# CPU.net
KiCad netlist of a schematic drawn in Altium Designer
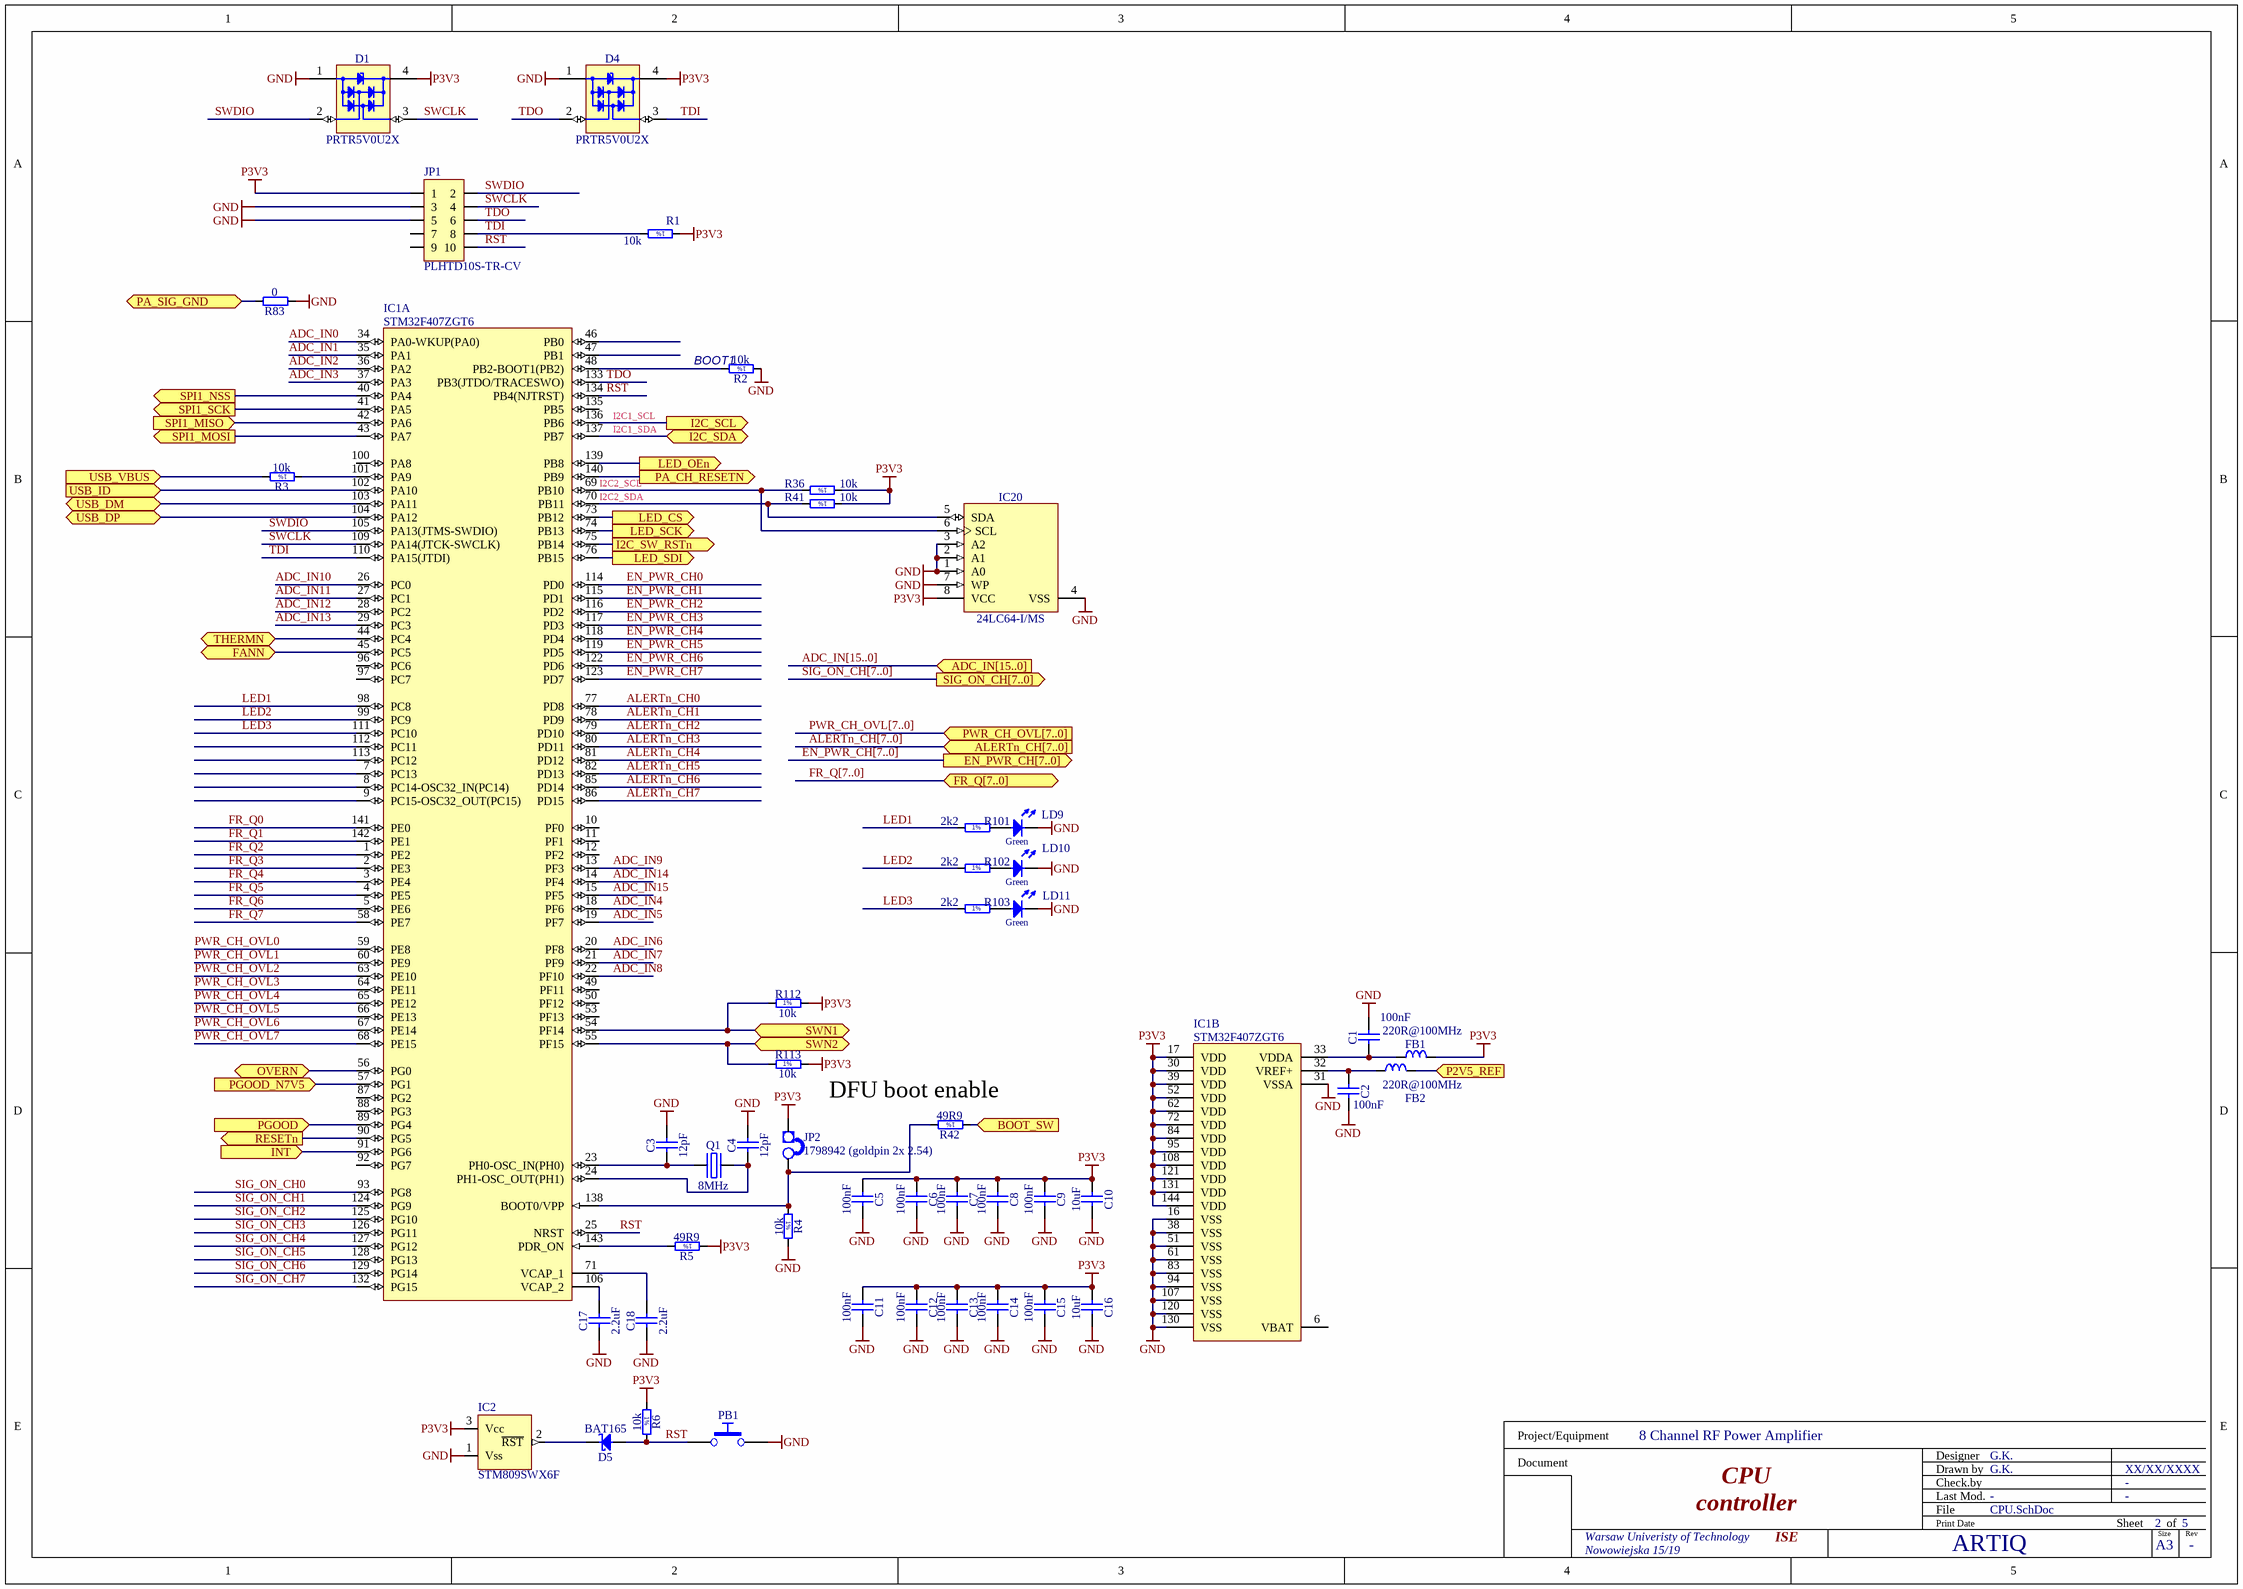
[diagram p0: CPU.SchDoc]

(export (version "E")
  (design (tool "Eeschema 10.0.6"))
  (components
    (comp (ref "C1")
      (value "100nF")
      (footprint "CAPC1005X55N")
      (description "Non-polarised capacitor")
      (fields
        (field (name "PART NUMBER") "CC0402_100NF_16V_10%_X7R")
        (field (name "VOLTAGE") "16V")
        (field (name "AUTHOR") "CERN DEM JLC")
      )
      (libsource (lib "Capacitors") (part "Capacitor - non polarized"))
    )
    (comp (ref "C2")
      (value "100nF")
      (footprint "CAPC1005X55N")
      (description "Non-polarised capacitor")
      (fields
        (field (name "PART NUMBER") "CC0402_100NF_16V_10%_X7R")
        (field (name "VOLTAGE") "16V")
        (field (name "AUTHOR") "CERN DEM JLC")
      )
      (libsource (lib "Capacitors") (part "Capacitor - non polarized"))
    )
    (comp (ref "C3")
      (value "12pF")
      (footprint "CAPC1005X55N")
      (description "Non-polarised capacitor")
      (fields
        (field (name "PART NUMBER") "CC0402_12PF_50V_5%_C0G")
        (field (name "VOLTAGE") "50V")
        (field (name "AUTHOR") "CERN DEM JLC")
      )
      (libsource (lib "Capacitors") (part "Capacitor - non polarized"))
    )
    (comp (ref "C4")
      (value "12pF")
      (footprint "CAPC1005X55N")
      (description "Non-polarised capacitor")
      (fields
        (field (name "PART NUMBER") "CC0402_12PF_50V_5%_C0G")
        (field (name "VOLTAGE") "50V")
        (field (name "AUTHOR") "CERN DEM JLC")
      )
      (libsource (lib "Capacitors") (part "Capacitor - non polarized"))
    )
    (comp (ref "C5")
      (value "100nF")
      (footprint "CAPC1005X55N")
      (description "Non-polarised capacitor")
      (fields
        (field (name "PART NUMBER") "CC0402_100NF_16V_10%_X7R")
        (field (name "VOLTAGE") "16V")
        (field (name "AUTHOR") "CERN DEM JLC")
      )
      (libsource (lib "Capacitors") (part "Capacitor - non polarized"))
    )
    (comp (ref "C6")
      (value "100nF")
      (footprint "CAPC1005X55N")
      (description "Non-polarised capacitor")
      (fields
        (field (name "PART NUMBER") "CC0402_100NF_16V_10%_X7R")
        (field (name "VOLTAGE") "16V")
        (field (name "AUTHOR") "CERN DEM JLC")
      )
      (libsource (lib "Capacitors") (part "Capacitor - non polarized"))
    )
    (comp (ref "C7")
      (value "100nF")
      (footprint "CAPC1005X55N")
      (description "Non-polarised capacitor")
      (fields
        (field (name "PART NUMBER") "CC0402_100NF_16V_10%_X7R")
        (field (name "VOLTAGE") "16V")
        (field (name "AUTHOR") "CERN DEM JLC")
      )
      (libsource (lib "Capacitors") (part "Capacitor - non polarized"))
    )
    (comp (ref "C8")
      (value "100nF")
      (footprint "CAPC1005X55N")
      (description "Non-polarised capacitor")
      (fields
        (field (name "PART NUMBER") "CC0402_100NF_16V_10%_X7R")
        (field (name "VOLTAGE") "16V")
        (field (name "AUTHOR") "CERN DEM JLC")
      )
      (libsource (lib "Capacitors") (part "Capacitor - non polarized"))
    )
    (comp (ref "C9")
      (value "100nF")
      (footprint "CAPC1005X55N")
      (description "Non-polarised capacitor")
      (fields
        (field (name "PART NUMBER") "CC0402_100NF_16V_10%_X7R")
        (field (name "VOLTAGE") "16V")
        (field (name "AUTHOR") "CERN DEM JLC")
      )
      (libsource (lib "Capacitors") (part "Capacitor - non polarized"))
    )
    (comp (ref "C10")
      (value "10uF")
      (footprint "CAPC2012X135N")
      (description "Non-polarised capacitor")
      (fields
        (field (name "PART NUMBER") "CC0805_10UF_16V_10%_X5R")
        (field (name "VOLTAGE") "16V")
        (field (name "AUTHOR") "CERN DEM JLC")
      )
      (libsource (lib "Capacitors") (part "Capacitor - non polarized"))
    )
    (comp (ref "C11")
      (value "100nF")
      (footprint "CAPC1005X55N")
      (description "Non-polarised capacitor")
      (fields
        (field (name "PART NUMBER") "CC0402_100NF_16V_10%_X7R")
        (field (name "VOLTAGE") "16V")
        (field (name "AUTHOR") "CERN DEM JLC")
      )
      (libsource (lib "Capacitors") (part "Capacitor - non polarized"))
    )
    (comp (ref "C12")
      (value "100nF")
      (footprint "CAPC1005X55N")
      (description "Non-polarised capacitor")
      (fields
        (field (name "PART NUMBER") "CC0402_100NF_16V_10%_X7R")
        (field (name "VOLTAGE") "16V")
        (field (name "AUTHOR") "CERN DEM JLC")
      )
      (libsource (lib "Capacitors") (part "Capacitor - non polarized"))
    )
    (comp (ref "C13")
      (value "100nF")
      (footprint "CAPC1005X55N")
      (description "Non-polarised capacitor")
      (fields
        (field (name "PART NUMBER") "CC0402_100NF_16V_10%_X7R")
        (field (name "VOLTAGE") "16V")
        (field (name "AUTHOR") "CERN DEM JLC")
      )
      (libsource (lib "Capacitors") (part "Capacitor - non polarized"))
    )
    (comp (ref "C14")
      (value "100nF")
      (footprint "CAPC1005X55N")
      (description "Non-polarised capacitor")
      (fields
        (field (name "PART NUMBER") "CC0402_100NF_16V_10%_X7R")
        (field (name "VOLTAGE") "16V")
        (field (name "AUTHOR") "CERN DEM JLC")
      )
      (libsource (lib "Capacitors") (part "Capacitor - non polarized"))
    )
    (comp (ref "C15")
      (value "100nF")
      (footprint "CAPC1005X55N")
      (description "Non-polarised capacitor")
      (fields
        (field (name "PART NUMBER") "CC0402_100NF_16V_10%_X7R")
        (field (name "VOLTAGE") "16V")
        (field (name "AUTHOR") "CERN DEM JLC")
      )
      (libsource (lib "Capacitors") (part "Capacitor - non polarized"))
    )
    (comp (ref "C16")
      (value "10uF")
      (footprint "CAPC2012X135N")
      (description "Non-polarised capacitor")
      (fields
        (field (name "PART NUMBER") "CC0805_10UF_16V_10%_X5R")
        (field (name "VOLTAGE") "16V")
        (field (name "AUTHOR") "CERN DEM JLC")
      )
      (libsource (lib "Capacitors") (part "Capacitor - non polarized"))
    )
    (comp (ref "C17")
      (value "2.2uF")
      (footprint "CAPC1608X90N")
      (description "Non-polarised capacitor")
      (fields
        (field (name "PART NUMBER") "CC0603_2.2UF_10V_20%_X7R")
        (field (name "VOLTAGE") "10V")
        (field (name "AUTHOR") "CERN DEM JLC")
      )
      (libsource (lib "Capacitors") (part "Capacitor - non polarized"))
    )
    (comp (ref "C18")
      (value "2.2uF")
      (footprint "CAPC1608X90N")
      (description "Non-polarised capacitor")
      (fields
        (field (name "PART NUMBER") "CC0603_2.2UF_10V_20%_X7R")
        (field (name "VOLTAGE") "10V")
        (field (name "AUTHOR") "CERN DEM JLC")
      )
      (libsource (lib "Capacitors") (part "Capacitor - non polarized"))
    )
    (comp (ref "D1")
      (value "PRTR5V0U2X")
      (footprint "SOT190P230X110-4N")
      (description "Ultra Low Capacitance Double Rail-to-Rail ESD Protection Diode")
      (fields
        (field (name "VOLTAGE") "5.5V")
        (field (name "MANUFACTURER") "NXP SEMICONDUCTORS")
        (field (name "AUTHOR") "CERN DEM JLC")
      )
      (libsource (lib "ICs And Semiconductors") (part "PRTR5V0U2X"))
    )
    (comp (ref "D4")
      (value "PRTR5V0U2X")
      (footprint "SOT190P230X110-4N")
      (description "Ultra Low Capacitance Double Rail-to-Rail ESD Protection Diode")
      (fields
        (field (name "VOLTAGE") "5.5V")
        (field (name "MANUFACTURER") "NXP SEMICONDUCTORS")
        (field (name "AUTHOR") "CERN DEM JLC")
      )
      (libsource (lib "ICs And Semiconductors") (part "PRTR5V0U2X"))
    )
    (comp (ref "D5")
      (value "BAT165")
      (footprint "SOD2512X110N")
      (description "Schottky Diode")
      (fields
        (field (name "VOLTAGE") "40V")
        (field (name "POWER") "750mA")
        (field (name "AUTHOR") "CERN DEM JLC")
      )
      (libsource (lib "ICs And Semiconductors") (part "Diode Schottky"))
    )
    (comp (ref "FB1")
      (value "220R@100MHz")
      (footprint "INDC2012X105N")
      (description "Inductor")
      (fields
        (field (name "PART NUMBER") "IND0805_MURATA_BLM21PG221SN1D")
        (field (name "POWER") "2A")
        (field (name "AUTHOR") "CERN DEM JLC")
      )
      (libsource (lib "Inductors & Transformers") (part "Inductor"))
    )
    (comp (ref "FB2")
      (value "220R@100MHz")
      (footprint "INDC2012X105N")
      (description "Inductor")
      (fields
        (field (name "PART NUMBER") "IND0805_MURATA_BLM21PG221SN1D")
        (field (name "POWER") "2A")
        (field (name "AUTHOR") "CERN DEM JLC")
      )
      (libsource (lib "Inductors & Transformers") (part "Inductor"))
    )
    (comp (ref "IC1")
      (value "STM32F407ZGT6")
      (footprint "QFP50P2200X2200X160-144N")
      (fields (field (name "MANUFACTURER") "ST MICROELECTRONICS") (field (name "AUTHOR") "CERN DEM MR"))
      (libsource (lib "ICs And Semiconductors") (part "STM32F407ZGT6"))
    )
    (comp (ref "IC2")
      (value "STM809SWX6F")
      (footprint "SOT-23")
      (description "2.93V  Reset circuit")
      (libsource (lib "LIBRARY_SCH") (part "VMON_STM809"))
    )
    (comp (ref "IC20")
      (value "24LC64-I/MS")
      (footprint "SOP65P490X110-8N")
      (description "64K I2C Serial EEPROM")
      (fields (field (name "MANUFACTURER") "MICROCHIP TECHNOLOGY") (field (name "AUTHOR") "CERN DEM JLC"))
      (libsource (lib "ICs And Semiconductors") (part "24LC64-I/MS"))
    )
    (comp (ref "JP1")
      (value "PLHTD10S-TR-CV")
      (footprint "PLHTD10S-TR-CV")
      (description "1.27 mm dual row goldpin (Maritex)")
      (libsource (lib "LIBRARY_SCH") (part "CON_2x5 1.27 SMT Male"))
    )
    (comp (ref "JP2")
      (value "1798942 (goldpin 2x 2.54)")
      (footprint "jump")
      (description "Jumper")
      (libsource (lib "LIBRARY_SCH") (part "JUMPER"))
    )
    (comp (ref "LD9")
      (value "Green")
      (footprint "LED_OSRAM_LGL29K")
      (description "LED Green 1C 2A")
      (fields
        (field (name "PART NUMBER") "LED_OSRAM_LG L29K-G2J1-24-Z")
        (field (name "MANUFACTURER") "OSRAM")
        (field (name "AUTHOR") "CERN DEM JLC")
      )
      (libsource (lib "ICs And Semiconductors") (part "LED Green 1C 2A"))
    )
    (comp (ref "LD10")
      (value "Green")
      (footprint "LED_OSRAM_LGL29K")
      (description "LED Green 1C 2A")
      (fields
        (field (name "PART NUMBER") "LED_OSRAM_LG L29K-G2J1-24-Z")
        (field (name "MANUFACTURER") "OSRAM")
        (field (name "AUTHOR") "CERN DEM JLC")
      )
      (libsource (lib "ICs And Semiconductors") (part "LED Green 1C 2A"))
    )
    (comp (ref "LD11")
      (value "Green")
      (footprint "LED_OSRAM_LGL29K")
      (description "LED Green 1C 2A")
      (fields
        (field (name "PART NUMBER") "LED_OSRAM_LG L29K-G2J1-24-Z")
        (field (name "MANUFACTURER") "OSRAM")
        (field (name "AUTHOR") "CERN DEM JLC")
      )
      (libsource (lib "ICs And Semiconductors") (part "LED Green 1C 2A"))
    )
    (comp (ref "PB1")
      (value "Push Button")
      (footprint "PB_TYCO_FSMSM")
      (description "Push-Button Switch SPDT")
      (fields
        (field (name "PART NUMBER") "PB_TYCO_FSMSM")
        (field (name "MANUFACTURER") "TYCO ELECTRONICS")
        (field (name "AUTHOR") "CERN DEM JLC")
      )
      (libsource (lib "Eletro-mechanical") (part "PB SPST 1NO-2NO"))
    )
    (comp (ref "Q1")
      (value "8MHz")
      (footprint "XTAL_TXC_7A")
      (description "Quartz Crystal")
      (fields
        (field (name "PART NUMBER") "XTAL_8MHZ_TXC_7A-8.000MAAE-T")
        (field (name "MANUFACTURER") "TXC CORPORATION")
        (field (name "AUTHOR") "CERN DEM JLC")
      )
      (libsource (lib "ICs And Semiconductors") (part "Quartz Crystal"))
    )
    (comp (ref "R1")
      (value "10k")
      (footprint "RESC1005X40N")
      (description "Resistor - 1%")
      (fields
        (field (name "PART NUMBER") "R0402_10K_1%_0.0625W_100PPM")
        (field (name "POWER") "0.0625W")
        (field (name "AUTHOR") "CERN DEM JLC")
      )
      (libsource (lib "Resistors") (part "Resistor - 1%"))
    )
    (comp (ref "R2")
      (value "10k")
      (footprint "RESC1005X40N")
      (description "Resistor - 1%")
      (fields
        (field (name "PART NUMBER") "R0402_10K_1%_0.0625W_100PPM")
        (field (name "POWER") "0.0625W")
        (field (name "AUTHOR") "CERN DEM JLC")
      )
      (libsource (lib "Resistors") (part "Resistor - 1%"))
    )
    (comp (ref "R3")
      (value "10k")
      (footprint "RESC1005X40N")
      (description "Resistor - 1%")
      (fields
        (field (name "PART NUMBER") "R0402_10K_1%_0.0625W_100PPM")
        (field (name "POWER") "0.0625W")
        (field (name "AUTHOR") "CERN DEM JLC")
      )
      (libsource (lib "Resistors") (part "Resistor - 1%"))
    )
    (comp (ref "R4")
      (value "10k")
      (footprint "RESC1005X40N")
      (description "Resistor - 1%")
      (fields
        (field (name "PART NUMBER") "R0402_10K_1%_0.0625W_100PPM")
        (field (name "POWER") "0.0625W")
        (field (name "AUTHOR") "CERN DEM JLC")
      )
      (libsource (lib "Resistors") (part "Resistor - 1%"))
    )
    (comp (ref "R5")
      (value "49R9")
      (footprint "RESC1005X40N")
      (description "Resistor - 1%")
      (fields
        (field (name "PART NUMBER") "R0402_49R9_1%_0.0625W_100PPM")
        (field (name "POWER") "0.0625W")
        (field (name "AUTHOR") "CERN DEM JLC")
      )
      (libsource (lib "Resistors") (part "Resistor - 1%"))
    )
    (comp (ref "R6")
      (value "10k")
      (footprint "RESC1005X40N")
      (description "Resistor - 1%")
      (fields
        (field (name "PART NUMBER") "R0402_10K_1%_0.0625W_100PPM")
        (field (name "POWER") "0.0625W")
        (field (name "AUTHOR") "CERN DEM JLC")
      )
      (libsource (lib "Resistors") (part "Resistor - 1%"))
    )
    (comp (ref "R36")
      (value "10k")
      (footprint "RESC1005X40N")
      (description "Resistor - 1%")
      (fields
        (field (name "PART NUMBER") "R0402_10K_1%_0.0625W_100PPM")
        (field (name "POWER") "0.0625W")
        (field (name "AUTHOR") "CERN DEM JLC")
      )
      (libsource (lib "Resistors") (part "Resistor - 1%"))
    )
    (comp (ref "R41")
      (value "10k")
      (footprint "RESC1005X40N")
      (description "Resistor - 1%")
      (fields
        (field (name "PART NUMBER") "R0402_10K_1%_0.0625W_100PPM")
        (field (name "POWER") "0.0625W")
        (field (name "AUTHOR") "CERN DEM JLC")
      )
      (libsource (lib "Resistors") (part "Resistor - 1%"))
    )
    (comp (ref "R42")
      (value "49R9")
      (footprint "RESC1005X40N")
      (description "Resistor - 1%")
      (fields
        (field (name "PART NUMBER") "R0402_49R9_1%_0.0625W_100PPM")
        (field (name "POWER") "0.0625W")
        (field (name "AUTHOR") "CERN DEM JLC")
      )
      (libsource (lib "Resistors") (part "Resistor - 1%"))
    )
    (comp (ref "R83")
      (value "0")
      (footprint "RESC1005X40N")
      (description "Resistor")
      (fields
        (field (name "PART NUMBER") "R0402_0R_JUMPER")
        (field (name "MANUFACTURER") "GENERIC")
        (field (name "AUTHOR") "CERN DEM JLC")
      )
      (libsource (lib "Resistors") (part "Resistor"))
    )
    (comp (ref "R101")
      (value "2k2")
      (footprint "RESC1005X40N")
      (description "Resistor - 1%")
      (fields
        (field (name "PART NUMBER") "R0402_2K2_1%_0.0625W_100PPM")
        (field (name "POWER") "0.0625W")
        (field (name "AUTHOR") "CERN DEM JLC")
      )
      (libsource (lib "Resistors") (part "Resistor - 1%"))
    )
    (comp (ref "R102")
      (value "2k2")
      (footprint "RESC1005X40N")
      (description "Resistor - 1%")
      (fields
        (field (name "PART NUMBER") "R0402_2K2_1%_0.0625W_100PPM")
        (field (name "POWER") "0.0625W")
        (field (name "AUTHOR") "CERN DEM JLC")
      )
      (libsource (lib "Resistors") (part "Resistor - 1%"))
    )
    (comp (ref "R103")
      (value "2k2")
      (footprint "RESC1005X40N")
      (description "Resistor - 1%")
      (fields
        (field (name "PART NUMBER") "R0402_2K2_1%_0.0625W_100PPM")
        (field (name "POWER") "0.0625W")
        (field (name "AUTHOR") "CERN DEM JLC")
      )
      (libsource (lib "Resistors") (part "Resistor - 1%"))
    )
    (comp (ref "R112")
      (value "10k")
      (footprint "RESC1005X40N")
      (description "Resistor - 1%")
      (fields
        (field (name "PART NUMBER") "R0402_10K_1%_0.0625W_100PPM")
        (field (name "POWER") "0.0625W")
        (field (name "AUTHOR") "CERN DEM JLC")
      )
      (libsource (lib "Resistors") (part "Resistor - 1%"))
    )
    (comp (ref "R113")
      (value "10k")
      (footprint "RESC1005X40N")
      (description "Resistor - 1%")
      (fields
        (field (name "PART NUMBER") "R0402_10K_1%_0.0625W_100PPM")
        (field (name "POWER") "0.0625W")
        (field (name "AUTHOR") "CERN DEM JLC")
      )
      (libsource (lib "Resistors") (part "Resistor - 1%"))
    )
  )
  (nets
    (net (code "1") (name "/ADC_IN0") (class "Default")
      (node (ref "IC1") (pin "34") (pinfunction "PA0-WKUP(PA0)_34") (pintype "bidirectional"))
    )
    (net (code "2") (name "/ADC_IN1") (class "Default")
      (node (ref "IC1") (pin "35") (pinfunction "PA1_35") (pintype "bidirectional"))
    )
    (net (code "3") (name "/ADC_IN2") (class "Default")
      (node (ref "IC1") (pin "36") (pinfunction "PA2_36") (pintype "bidirectional"))
    )
    (net (code "4") (name "/ADC_IN3") (class "Default")
      (node (ref "IC1") (pin "37") (pinfunction "PA3_37") (pintype "bidirectional"))
    )
    (net (code "5") (name "/ADC_IN4") (class "Default")
      (node (ref "IC1") (pin "18") (pinfunction "PF6_18") (pintype "bidirectional"))
    )
    (net (code "6") (name "/ADC_IN5") (class "Default")
      (node (ref "IC1") (pin "19") (pinfunction "PF7_19") (pintype "bidirectional"))
    )
    (net (code "7") (name "/ADC_IN6") (class "Default")
      (node (ref "IC1") (pin "20") (pinfunction "PF8_20") (pintype "bidirectional"))
    )
    (net (code "8") (name "/ADC_IN7") (class "Default")
      (node (ref "IC1") (pin "21") (pinfunction "PF9_21") (pintype "bidirectional"))
    )
    (net (code "9") (name "/ADC_IN8") (class "Default")
      (node (ref "IC1") (pin "22") (pinfunction "PF10_22") (pintype "bidirectional"))
    )
    (net (code "10") (name "/ADC_IN9") (class "Default")
      (node (ref "IC1") (pin "13") (pinfunction "PF3_13") (pintype "bidirectional"))
    )
    (net (code "11") (name "/ADC_IN10") (class "Default")
      (node (ref "IC1") (pin "26") (pinfunction "PC0_26") (pintype "bidirectional"))
    )
    (net (code "12") (name "/ADC_IN11") (class "Default")
      (node (ref "IC1") (pin "27") (pinfunction "PC1_27") (pintype "bidirectional"))
    )
    (net (code "13") (name "/ADC_IN12") (class "Default")
      (node (ref "IC1") (pin "28") (pinfunction "PC2_28") (pintype "bidirectional"))
    )
    (net (code "14") (name "/ADC_IN13") (class "Default")
      (node (ref "IC1") (pin "29") (pinfunction "PC3_29") (pintype "bidirectional"))
    )
    (net (code "15") (name "/ADC_IN14") (class "Default")
      (node (ref "IC1") (pin "14") (pinfunction "PF4_14") (pintype "bidirectional"))
    )
    (net (code "16") (name "/ADC_IN15") (class "Default")
      (node (ref "IC1") (pin "15") (pinfunction "PF5_15") (pintype "bidirectional"))
    )
    (net (code "18") (name "/ALERTn_CH0") (class "Default")
      (node (ref "IC1") (pin "77") (pinfunction "PD8_77") (pintype "bidirectional"))
    )
    (net (code "19") (name "/ALERTn_CH1") (class "Default")
      (node (ref "IC1") (pin "78") (pinfunction "PD9_78") (pintype "bidirectional"))
    )
    (net (code "20") (name "/ALERTn_CH2") (class "Default")
      (node (ref "IC1") (pin "79") (pinfunction "PD10_79") (pintype "bidirectional"))
    )
    (net (code "21") (name "/ALERTn_CH3") (class "Default")
      (node (ref "IC1") (pin "80") (pinfunction "PD11_80") (pintype "bidirectional"))
    )
    (net (code "22") (name "/ALERTn_CH4") (class "Default")
      (node (ref "IC1") (pin "81") (pinfunction "PD12_81") (pintype "bidirectional"))
    )
    (net (code "23") (name "/ALERTn_CH5") (class "Default")
      (node (ref "IC1") (pin "82") (pinfunction "PD13_82") (pintype "bidirectional"))
    )
    (net (code "24") (name "/ALERTn_CH6") (class "Default")
      (node (ref "IC1") (pin "85") (pinfunction "PD14_85") (pintype "bidirectional"))
    )
    (net (code "25") (name "/ALERTn_CH7") (class "Default")
      (node (ref "IC1") (pin "86") (pinfunction "PD15_86") (pintype "bidirectional"))
    )
    (net (code "27") (name "/BOOT_SW") (class "Default")
      (node (ref "R42") (pin "1") (pinfunction "1_1") (pintype "passive"))
    )
    (net (code "28") (name "/EN_PWR_CH0") (class "Default")
      (node (ref "IC1") (pin "114") (pinfunction "PD0_114") (pintype "bidirectional"))
    )
    (net (code "29") (name "/EN_PWR_CH1") (class "Default")
      (node (ref "IC1") (pin "115") (pinfunction "PD1_115") (pintype "bidirectional"))
    )
    (net (code "30") (name "/EN_PWR_CH2") (class "Default")
      (node (ref "IC1") (pin "116") (pinfunction "PD2_116") (pintype "bidirectional"))
    )
    (net (code "31") (name "/EN_PWR_CH3") (class "Default")
      (node (ref "IC1") (pin "117") (pinfunction "PD3_117") (pintype "bidirectional"))
    )
    (net (code "32") (name "/EN_PWR_CH4") (class "Default")
      (node (ref "IC1") (pin "118") (pinfunction "PD4_118") (pintype "bidirectional"))
    )
    (net (code "33") (name "/EN_PWR_CH5") (class "Default")
      (node (ref "IC1") (pin "119") (pinfunction "PD5_119") (pintype "bidirectional"))
    )
    (net (code "34") (name "/EN_PWR_CH6") (class "Default")
      (node (ref "IC1") (pin "122") (pinfunction "PD6_122") (pintype "bidirectional"))
    )
    (net (code "35") (name "/EN_PWR_CH7") (class "Default")
      (node (ref "IC1") (pin "123") (pinfunction "PD7_123") (pintype "bidirectional"))
    )
    (net (code "37") (name "/FANN") (class "Default")
      (node (ref "IC1") (pin "45") (pinfunction "PC5_45") (pintype "bidirectional"))
    )
    (net (code "38") (name "/FR_Q0") (class "Default")
      (node (ref "IC1") (pin "141") (pinfunction "PE0_141") (pintype "bidirectional"))
    )
    (net (code "39") (name "/FR_Q1") (class "Default")
      (node (ref "IC1") (pin "142") (pinfunction "PE1_142") (pintype "bidirectional"))
    )
    (net (code "40") (name "/FR_Q2") (class "Default")
      (node (ref "IC1") (pin "1") (pinfunction "PE2_1") (pintype "bidirectional"))
    )
    (net (code "41") (name "/FR_Q3") (class "Default")
      (node (ref "IC1") (pin "2") (pinfunction "PE3_2") (pintype "bidirectional"))
    )
    (net (code "42") (name "/FR_Q4") (class "Default")
      (node (ref "IC1") (pin "3") (pinfunction "PE4_3") (pintype "bidirectional"))
    )
    (net (code "43") (name "/FR_Q5") (class "Default")
      (node (ref "IC1") (pin "4") (pinfunction "PE5_4") (pintype "bidirectional"))
    )
    (net (code "44") (name "/FR_Q6") (class "Default")
      (node (ref "IC1") (pin "5") (pinfunction "PE6_5") (pintype "bidirectional"))
    )
    (net (code "45") (name "/FR_Q7") (class "Default")
      (node (ref "IC1") (pin "58") (pinfunction "PE7_58") (pintype "bidirectional"))
    )
    (net (code "47") (name "/I2C_SCL") (class "Default")
      (node (ref "IC1") (pin "136") (pinfunction "PB6_136") (pintype "bidirectional"))
    )
    (net (code "48") (name "/I2C_SDA") (class "Default")
      (node (ref "IC1") (pin "137") (pinfunction "PB7_137") (pintype "bidirectional"))
    )
    (net (code "49") (name "/I2C_SW_RSTn") (class "Default")
      (node (ref "IC1") (pin "75") (pinfunction "PB14_75") (pintype "bidirectional"))
    )
    (net (code "50") (name "/INT") (class "Default")
      (node (ref "IC1") (pin "91") (pinfunction "PG6_91") (pintype "bidirectional"))
    )
    (net (code "51") (name "/LED1") (class "Default")
      (node (ref "IC1") (pin "98") (pinfunction "PC8_98") (pintype "bidirectional"))
      (node (ref "R101") (pin "1") (pinfunction "1_1") (pintype "passive"))
    )
    (net (code "52") (name "/LED2") (class "Default")
      (node (ref "IC1") (pin "99") (pinfunction "PC9_99") (pintype "bidirectional"))
      (node (ref "R102") (pin "1") (pinfunction "1_1") (pintype "passive"))
    )
    (net (code "53") (name "/LED3") (class "Default")
      (node (ref "IC1") (pin "111") (pinfunction "PC10_111") (pintype "bidirectional"))
      (node (ref "R103") (pin "1") (pinfunction "1_1") (pintype "passive"))
    )
    (net (code "54") (name "/LED_CS") (class "Default")
      (node (ref "IC1") (pin "73") (pinfunction "PB12_73") (pintype "bidirectional"))
    )
    (net (code "55") (name "/LED_OEn") (class "Default")
      (node (ref "IC1") (pin "139") (pinfunction "PB8_139") (pintype "bidirectional"))
    )
    (net (code "56") (name "/LED_SCK") (class "Default")
      (node (ref "IC1") (pin "74") (pinfunction "PB13_74") (pintype "bidirectional"))
    )
    (net (code "57") (name "/LED_SDI") (class "Default")
      (node (ref "IC1") (pin "76") (pinfunction "PB15_76") (pintype "bidirectional"))
    )
    (net (code "58") (name "/OVERN") (class "Default")
      (node (ref "IC1") (pin "56") (pinfunction "PG0_56") (pintype "bidirectional"))
    )
    (net (code "59") (name "/P2V5_REF") (class "Default")
      (node (ref "FB2") (pin "2") (pinfunction "2_2") (pintype "passive"))
    )
    (net (code "60") (name "/PA_CH_RESETN") (class "Default")
      (node (ref "IC1") (pin "140") (pinfunction "PB9_140") (pintype "bidirectional"))
    )
    (net (code "61") (name "/PA_SIG_GND") (class "Default")
      (node (ref "R83") (pin "2") (pinfunction "2_2") (pintype "passive"))
    )
    (net (code "62") (name "/PGOOD") (class "Default")
      (node (ref "IC1") (pin "89") (pinfunction "PG4_89") (pintype "bidirectional"))
    )
    (net (code "63") (name "/PGOOD_N7V5") (class "Default")
      (node (ref "IC1") (pin "57") (pinfunction "PG1_57") (pintype "bidirectional"))
    )
    (net (code "64") (name "/PWR_CH_OVL0") (class "Default")
      (node (ref "IC1") (pin "59") (pinfunction "PE8_59") (pintype "bidirectional"))
    )
    (net (code "65") (name "/PWR_CH_OVL1") (class "Default")
      (node (ref "IC1") (pin "60") (pinfunction "PE9_60") (pintype "bidirectional"))
    )
    (net (code "66") (name "/PWR_CH_OVL2") (class "Default")
      (node (ref "IC1") (pin "63") (pinfunction "PE10_63") (pintype "bidirectional"))
    )
    (net (code "67") (name "/PWR_CH_OVL3") (class "Default")
      (node (ref "IC1") (pin "64") (pinfunction "PE11_64") (pintype "bidirectional"))
    )
    (net (code "68") (name "/PWR_CH_OVL4") (class "Default")
      (node (ref "IC1") (pin "65") (pinfunction "PE12_65") (pintype "bidirectional"))
    )
    (net (code "69") (name "/PWR_CH_OVL5") (class "Default")
      (node (ref "IC1") (pin "66") (pinfunction "PE13_66") (pintype "bidirectional"))
    )
    (net (code "70") (name "/PWR_CH_OVL6") (class "Default")
      (node (ref "IC1") (pin "67") (pinfunction "PE14_67") (pintype "bidirectional"))
    )
    (net (code "71") (name "/PWR_CH_OVL7") (class "Default")
      (node (ref "IC1") (pin "68") (pinfunction "PE15_68") (pintype "bidirectional"))
    )
    (net (code "73") (name "/RESETn") (class "Default")
      (node (ref "IC1") (pin "90") (pinfunction "PG5_90") (pintype "bidirectional"))
    )
    (net (code "74") (name "/RST") (class "Default")
      (node (ref "D5") (pin "2") (pinfunction "A_2") (pintype "passive"))
      (node (ref "IC1") (pin "134") (pinfunction "PB4(NJTRST)_134") (pintype "bidirectional"))
      (node (ref "IC1") (pin "25") (pinfunction "NRST_25") (pintype "bidirectional"))
      (node (ref "JP1") (pin "10") (pinfunction "10_10") (pintype "passive"))
      (node (ref "PB1") (pin "1") (pinfunction "1_1") (pintype "passive"))
      (node (ref "R6") (pin "2") (pinfunction "2_2") (pintype "passive"))
    )
    (net (code "75") (name "/SIG_ON_CH0") (class "Default")
      (node (ref "IC1") (pin "93") (pinfunction "PG8_93") (pintype "bidirectional"))
    )
    (net (code "76") (name "/SIG_ON_CH1") (class "Default")
      (node (ref "IC1") (pin "124") (pinfunction "PG9_124") (pintype "bidirectional"))
    )
    (net (code "77") (name "/SIG_ON_CH2") (class "Default")
      (node (ref "IC1") (pin "125") (pinfunction "PG10_125") (pintype "bidirectional"))
    )
    (net (code "78") (name "/SIG_ON_CH3") (class "Default")
      (node (ref "IC1") (pin "126") (pinfunction "PG11_126") (pintype "bidirectional"))
    )
    (net (code "79") (name "/SIG_ON_CH4") (class "Default")
      (node (ref "IC1") (pin "127") (pinfunction "PG12_127") (pintype "bidirectional"))
    )
    (net (code "80") (name "/SIG_ON_CH5") (class "Default")
      (node (ref "IC1") (pin "128") (pinfunction "PG13_128") (pintype "bidirectional"))
    )
    (net (code "81") (name "/SIG_ON_CH6") (class "Default")
      (node (ref "IC1") (pin "129") (pinfunction "PG14_129") (pintype "bidirectional"))
    )
    (net (code "82") (name "/SIG_ON_CH7") (class "Default")
      (node (ref "IC1") (pin "132") (pinfunction "PG15_132") (pintype "bidirectional"))
    )
    (net (code "84") (name "/SPI1_MISO") (class "Default")
      (node (ref "IC1") (pin "42") (pinfunction "PA6_42") (pintype "bidirectional"))
    )
    (net (code "85") (name "/SPI1_MOSI") (class "Default")
      (node (ref "IC1") (pin "43") (pinfunction "PA7_43") (pintype "bidirectional"))
    )
    (net (code "86") (name "/SPI1_NSS") (class "Default")
      (node (ref "IC1") (pin "40") (pinfunction "PA4_40") (pintype "bidirectional"))
    )
    (net (code "87") (name "/SPI1_SCK") (class "Default")
      (node (ref "IC1") (pin "41") (pinfunction "PA5_41") (pintype "bidirectional"))
    )
    (net (code "88") (name "/SWCLK") (class "Default")
      (node (ref "D1") (pin "3") (pinfunction "I/O2_3") (pintype "bidirectional"))
      (node (ref "IC1") (pin "109") (pinfunction "PA14(JTCK-SWCLK)_109") (pintype "bidirectional"))
      (node (ref "JP1") (pin "4") (pinfunction "4_4") (pintype "passive"))
    )
    (net (code "89") (name "/SWDIO") (class "Default")
      (node (ref "D1") (pin "2") (pinfunction "I/O1_2") (pintype "bidirectional"))
      (node (ref "IC1") (pin "105") (pinfunction "PA13(JTMS-SWDIO)_105") (pintype "bidirectional"))
      (node (ref "JP1") (pin "2") (pinfunction "2_2") (pintype "passive"))
    )
    (net (code "90") (name "/SWN1") (class "Default")
      (node (ref "IC1") (pin "54") (pinfunction "PF14_54") (pintype "bidirectional"))
      (node (ref "R112") (pin "1") (pinfunction "1_1") (pintype "passive"))
    )
    (net (code "91") (name "/SWN2") (class "Default")
      (node (ref "IC1") (pin "55") (pinfunction "PF15_55") (pintype "bidirectional"))
      (node (ref "R113") (pin "1") (pinfunction "1_1") (pintype "passive"))
    )
    (net (code "92") (name "/TDI") (class "Default")
      (node (ref "D4") (pin "3") (pinfunction "I/O2_3") (pintype "bidirectional"))
      (node (ref "IC1") (pin "110") (pinfunction "PA15(JTDI)_110") (pintype "bidirectional"))
      (node (ref "JP1") (pin "8") (pinfunction "8_8") (pintype "passive"))
      (node (ref "R1") (pin "2") (pinfunction "2_2") (pintype "passive"))
    )
    (net (code "93") (name "/TDO") (class "Default")
      (node (ref "D4") (pin "2") (pinfunction "I/O1_2") (pintype "bidirectional"))
      (node (ref "IC1") (pin "133") (pinfunction "PB3(JTDO/TRACESWO)_133") (pintype "bidirectional"))
      (node (ref "JP1") (pin "6") (pinfunction "6_6") (pintype "passive"))
    )
    (net (code "94") (name "/THERMN") (class "Default")
      (node (ref "IC1") (pin "44") (pinfunction "PC4_44") (pintype "bidirectional"))
    )
    (net (code "95") (name "/USB_DM") (class "Default")
      (node (ref "IC1") (pin "103") (pinfunction "PA11_103") (pintype "bidirectional"))
    )
    (net (code "96") (name "/USB_DP") (class "Default")
      (node (ref "IC1") (pin "104") (pinfunction "PA12_104") (pintype "bidirectional"))
    )
    (net (code "97") (name "/USB_ID") (class "Default")
      (node (ref "IC1") (pin "102") (pinfunction "PA10_102") (pintype "bidirectional"))
    )
    (net (code "98") (name "/USB_VBUS") (class "Default")
      (node (ref "R3") (pin "2") (pinfunction "2_2") (pintype "passive"))
    )
    (net (code "99") (name "GND") (class "Default")
      (node (ref "C1") (pin "2") (pinfunction "2_2") (pintype "passive"))
      (node (ref "C10") (pin "2") (pinfunction "2_2") (pintype "passive"))
      (node (ref "C11") (pin "2") (pinfunction "2_2") (pintype "passive"))
      (node (ref "C12") (pin "2") (pinfunction "2_2") (pintype "passive"))
      (node (ref "C13") (pin "2") (pinfunction "2_2") (pintype "passive"))
      (node (ref "C14") (pin "2") (pinfunction "2_2") (pintype "passive"))
      (node (ref "C15") (pin "2") (pinfunction "2_2") (pintype "passive"))
      (node (ref "C16") (pin "2") (pinfunction "2_2") (pintype "passive"))
      (node (ref "C17") (pin "1") (pinfunction "1_1") (pintype "passive"))
      (node (ref "C18") (pin "1") (pinfunction "1_1") (pintype "passive"))
      (node (ref "C2") (pin "2") (pinfunction "2_2") (pintype "passive"))
      (node (ref "C3") (pin "2") (pinfunction "2_2") (pintype "passive"))
      (node (ref "C4") (pin "2") (pinfunction "2_2") (pintype "passive"))
      (node (ref "C5") (pin "2") (pinfunction "2_2") (pintype "passive"))
      (node (ref "C6") (pin "2") (pinfunction "2_2") (pintype "passive"))
      (node (ref "C7") (pin "2") (pinfunction "2_2") (pintype "passive"))
      (node (ref "C8") (pin "2") (pinfunction "2_2") (pintype "passive"))
      (node (ref "C9") (pin "2") (pinfunction "2_2") (pintype "passive"))
      (node (ref "D1") (pin "1") (pinfunction "GND_1") (pintype "power_in"))
      (node (ref "D4") (pin "1") (pinfunction "GND_1") (pintype "power_in"))
      (node (ref "IC1") (pin "107") (pinfunction "VSS_107") (pintype "power_in"))
      (node (ref "IC1") (pin "120") (pinfunction "VSS_120") (pintype "power_in"))
      (node (ref "IC1") (pin "130") (pinfunction "VSS_130") (pintype "power_in"))
      (node (ref "IC1") (pin "16") (pinfunction "VSS_16") (pintype "power_in"))
      (node (ref "IC1") (pin "31") (pinfunction "VSSA_31") (pintype "power_in"))
      (node (ref "IC1") (pin "38") (pinfunction "VSS_38") (pintype "power_in"))
      (node (ref "IC1") (pin "51") (pinfunction "VSS_51") (pintype "power_in"))
      (node (ref "IC1") (pin "61") (pinfunction "VSS_61") (pintype "power_in"))
      (node (ref "IC1") (pin "83") (pinfunction "VSS_83") (pintype "power_in"))
      (node (ref "IC1") (pin "94") (pinfunction "VSS_94") (pintype "power_in"))
      (node (ref "IC2") (pin "1") (pinfunction "Vss_1") (pintype "power_in"))
      (node (ref "IC20") (pin "1") (pinfunction "A0_1") (pintype "input"))
      (node (ref "IC20") (pin "2") (pinfunction "A1_2") (pintype "input"))
      (node (ref "IC20") (pin "3") (pinfunction "A2_3") (pintype "input"))
      (node (ref "IC20") (pin "4") (pinfunction "VSS_4") (pintype "power_in"))
      (node (ref "IC20") (pin "7") (pinfunction "WP_7") (pintype "input"))
      (node (ref "JP1") (pin "3") (pinfunction "3_3") (pintype "passive"))
      (node (ref "JP1") (pin "5") (pinfunction "5_5") (pintype "passive"))
      (node (ref "LD10") (pin "1") (pinfunction "C_1") (pintype "passive"))
      (node (ref "LD11") (pin "1") (pinfunction "C_1") (pintype "passive"))
      (node (ref "LD9") (pin "1") (pinfunction "C_1") (pintype "passive"))
      (node (ref "PB1") (pin "2") (pinfunction "2_2") (pintype "passive"))
      (node (ref "R2") (pin "1") (pinfunction "1_1") (pintype "passive"))
      (node (ref "R4") (pin "2") (pinfunction "2_2") (pintype "passive"))
      (node (ref "R83") (pin "1") (pinfunction "1_1") (pintype "passive"))
    )
    (net (code "100") (name "Net-(D5-C)") (class "Default")
      (node (ref "D5") (pin "1") (pinfunction "C_1") (pintype "passive"))
      (node (ref "IC2") (pin "2") (pinfunction "~{RST}_2") (pintype "output"))
    )
    (net (code "101") (name "Net-(IC1A-BOOT0{slash}VPP)") (class "Default")
      (node (ref "IC1") (pin "138") (pinfunction "BOOT0/VPP_138") (pintype "input"))
      (node (ref "JP2") (pin "2") (pinfunction "E2_2") (pintype "passive"))
      (node (ref "R4") (pin "1") (pinfunction "1_1") (pintype "passive"))
      (node (ref "R42") (pin "2") (pinfunction "2_2") (pintype "passive"))
    )
    (net (code "102") (name "Net-(IC1A-PA9)") (class "Default")
      (node (ref "IC1") (pin "101") (pinfunction "PA9_101") (pintype "bidirectional"))
      (node (ref "R3") (pin "1") (pinfunction "1_1") (pintype "passive"))
    )
    (net (code "103") (name "Net-(IC1A-PB2-BOOT1(PB2))") (class "Default")
      (node (ref "IC1") (pin "48") (pinfunction "PB2-BOOT1(PB2)_48") (pintype "bidirectional"))
      (node (ref "R2") (pin "2") (pinfunction "2_2") (pintype "passive"))
    )
    (net (code "104") (name "Net-(IC1A-PB10)") (class "Default")
      (node (ref "IC1") (pin "69") (pinfunction "PB10_69") (pintype "bidirectional"))
      (node (ref "IC20") (pin "6") (pinfunction "SCL_6") (pintype "input"))
      (node (ref "R36") (pin "2") (pinfunction "2_2") (pintype "passive"))
    )
    (net (code "105") (name "Net-(IC1A-PB11)") (class "Default")
      (node (ref "IC1") (pin "70") (pinfunction "PB11_70") (pintype "bidirectional"))
      (node (ref "IC20") (pin "5") (pinfunction "SDA_5") (pintype "bidirectional"))
      (node (ref "R41") (pin "2") (pinfunction "2_2") (pintype "passive"))
    )
    (net (code "106") (name "Net-(IC1A-PDR_ON)") (class "Default")
      (node (ref "IC1") (pin "143") (pinfunction "PDR_ON_143") (pintype "input"))
      (node (ref "R5") (pin "2") (pinfunction "2_2") (pintype "passive"))
    )
    (net (code "107") (name "Net-(IC1A-PH0-OSC_IN(PH0))") (class "Default")
      (node (ref "C3") (pin "1") (pinfunction "1_1") (pintype "passive"))
      (node (ref "IC1") (pin "23") (pinfunction "PH0-OSC_IN(PH0)_23") (pintype "bidirectional"))
      (node (ref "Q1") (pin "1") (pinfunction "OSC1_1") (pintype "passive"))
    )
    (net (code "108") (name "Net-(IC1A-PH1-OSC_OUT(PH1))") (class "Default")
      (node (ref "C4") (pin "1") (pinfunction "1_1") (pintype "passive"))
      (node (ref "IC1") (pin "24") (pinfunction "PH1-OSC_OUT(PH1)_24") (pintype "bidirectional"))
      (node (ref "Q1") (pin "2") (pinfunction "OSC2_2") (pintype "passive"))
    )
    (net (code "109") (name "Net-(IC1A-VCAP_1)") (class "Default")
      (node (ref "C18") (pin "2") (pinfunction "2_2") (pintype "passive"))
      (node (ref "IC1") (pin "71") (pinfunction "VCAP_1_71") (pintype "power_in"))
    )
    (net (code "110") (name "Net-(IC1A-VCAP_2)") (class "Default")
      (node (ref "C17") (pin "2") (pinfunction "2_2") (pintype "passive"))
      (node (ref "IC1") (pin "106") (pinfunction "VCAP_2_106") (pintype "power_in"))
    )
    (net (code "111") (name "Net-(IC1B-VDDA)") (class "Default")
      (node (ref "C1") (pin "1") (pinfunction "1_1") (pintype "passive"))
      (node (ref "FB1") (pin "1") (pinfunction "1_1") (pintype "passive"))
      (node (ref "IC1") (pin "33") (pinfunction "VDDA_33") (pintype "power_in"))
    )
    (net (code "112") (name "Net-(IC1B-VREF+)") (class "Default")
      (node (ref "C2") (pin "1") (pinfunction "1_1") (pintype "passive"))
      (node (ref "FB2") (pin "1") (pinfunction "1_1") (pintype "passive"))
      (node (ref "IC1") (pin "32") (pinfunction "VREF+_32") (pintype "power_in"))
    )
    (net (code "113") (name "Net-(LD9-A)") (class "Default")
      (node (ref "LD9") (pin "2") (pinfunction "A_2") (pintype "passive"))
      (node (ref "R101") (pin "2") (pinfunction "2_2") (pintype "passive"))
    )
    (net (code "114") (name "Net-(LD10-A)") (class "Default")
      (node (ref "LD10") (pin "2") (pinfunction "A_2") (pintype "passive"))
      (node (ref "R102") (pin "2") (pinfunction "2_2") (pintype "passive"))
    )
    (net (code "115") (name "Net-(LD11-A)") (class "Default")
      (node (ref "LD11") (pin "2") (pinfunction "A_2") (pintype "passive"))
      (node (ref "R103") (pin "2") (pinfunction "2_2") (pintype "passive"))
    )
    (net (code "116") (name "P3V3") (class "Default")
      (node (ref "C10") (pin "1") (pinfunction "1_1") (pintype "passive"))
      (node (ref "C11") (pin "1") (pinfunction "1_1") (pintype "passive"))
      (node (ref "C12") (pin "1") (pinfunction "1_1") (pintype "passive"))
      (node (ref "C13") (pin "1") (pinfunction "1_1") (pintype "passive"))
      (node (ref "C14") (pin "1") (pinfunction "1_1") (pintype "passive"))
      (node (ref "C15") (pin "1") (pinfunction "1_1") (pintype "passive"))
      (node (ref "C16") (pin "1") (pinfunction "1_1") (pintype "passive"))
      (node (ref "C5") (pin "1") (pinfunction "1_1") (pintype "passive"))
      (node (ref "C6") (pin "1") (pinfunction "1_1") (pintype "passive"))
      (node (ref "C7") (pin "1") (pinfunction "1_1") (pintype "passive"))
      (node (ref "C8") (pin "1") (pinfunction "1_1") (pintype "passive"))
      (node (ref "C9") (pin "1") (pinfunction "1_1") (pintype "passive"))
      (node (ref "D1") (pin "4") (pinfunction "VCC_4") (pintype "power_in"))
      (node (ref "D4") (pin "4") (pinfunction "VCC_4") (pintype "power_in"))
      (node (ref "FB1") (pin "2") (pinfunction "2_2") (pintype "passive"))
      (node (ref "IC1") (pin "108") (pinfunction "VDD_108") (pintype "power_in"))
      (node (ref "IC1") (pin "121") (pinfunction "VDD_121") (pintype "power_in"))
      (node (ref "IC1") (pin "131") (pinfunction "VDD_131") (pintype "power_in"))
      (node (ref "IC1") (pin "144") (pinfunction "VDD_144") (pintype "power_in"))
      (node (ref "IC1") (pin "17") (pinfunction "VDD_17") (pintype "power_in"))
      (node (ref "IC1") (pin "30") (pinfunction "VDD_30") (pintype "power_in"))
      (node (ref "IC1") (pin "39") (pinfunction "VDD_39") (pintype "power_in"))
      (node (ref "IC1") (pin "52") (pinfunction "VDD_52") (pintype "power_in"))
      (node (ref "IC1") (pin "62") (pinfunction "VDD_62") (pintype "power_in"))
      (node (ref "IC1") (pin "72") (pinfunction "VDD_72") (pintype "power_in"))
      (node (ref "IC1") (pin "84") (pinfunction "VDD_84") (pintype "power_in"))
      (node (ref "IC1") (pin "95") (pinfunction "VDD_95") (pintype "power_in"))
      (node (ref "IC2") (pin "3") (pinfunction "Vcc_3") (pintype "power_in"))
      (node (ref "IC20") (pin "8") (pinfunction "VCC_8") (pintype "power_in"))
      (node (ref "JP1") (pin "1") (pinfunction "1_1") (pintype "passive"))
      (node (ref "JP2") (pin "1") (pinfunction "E1_1") (pintype "passive"))
      (node (ref "R1") (pin "1") (pinfunction "1_1") (pintype "passive"))
      (node (ref "R112") (pin "2") (pinfunction "2_2") (pintype "passive"))
      (node (ref "R113") (pin "2") (pinfunction "2_2") (pintype "passive"))
      (node (ref "R36") (pin "1") (pinfunction "1_1") (pintype "passive"))
      (node (ref "R41") (pin "1") (pinfunction "1_1") (pintype "passive"))
      (node (ref "R5") (pin "1") (pinfunction "1_1") (pintype "passive"))
      (node (ref "R6") (pin "1") (pinfunction "1_1") (pintype "passive"))
    )
    (net (code "117") (name "unconnected-(IC1A-PA8-Pad100)") (class "Default")
      (node (ref "IC1") (pin "100") (pinfunction "PA8_100") (pintype "bidirectional"))
    )
    (net (code "118") (name "unconnected-(IC1A-PB0-Pad46)") (class "Default")
      (node (ref "IC1") (pin "46") (pinfunction "PB0_46") (pintype "bidirectional"))
    )
    (net (code "119") (name "unconnected-(IC1A-PB1-Pad47)") (class "Default")
      (node (ref "IC1") (pin "47") (pinfunction "PB1_47") (pintype "bidirectional"))
    )
    (net (code "120") (name "unconnected-(IC1A-PB5-Pad135)") (class "Default")
      (node (ref "IC1") (pin "135") (pinfunction "PB5_135") (pintype "bidirectional"))
    )
    (net (code "121") (name "unconnected-(IC1A-PC6-Pad96)") (class "Default")
      (node (ref "IC1") (pin "96") (pinfunction "PC6_96") (pintype "bidirectional"))
    )
    (net (code "122") (name "unconnected-(IC1A-PC7-Pad97)") (class "Default")
      (node (ref "IC1") (pin "97") (pinfunction "PC7_97") (pintype "bidirectional"))
    )
    (net (code "123") (name "unconnected-(IC1A-PC11-Pad112)") (class "Default")
      (node (ref "IC1") (pin "112") (pinfunction "PC11_112") (pintype "bidirectional"))
    )
    (net (code "124") (name "unconnected-(IC1A-PC12-Pad113)") (class "Default")
      (node (ref "IC1") (pin "113") (pinfunction "PC12_113") (pintype "bidirectional"))
    )
    (net (code "125") (name "unconnected-(IC1A-PC13-Pad7)") (class "Default")
      (node (ref "IC1") (pin "7") (pinfunction "PC13_7") (pintype "bidirectional"))
    )
    (net (code "126") (name "unconnected-(IC1A-PC14-OSC32_IN(PC14)-Pad8)") (class "Default")
      (node (ref "IC1") (pin "8") (pinfunction "PC14-OSC32_IN(PC14)_8") (pintype "bidirectional"))
    )
    (net (code "127") (name "unconnected-(IC1A-PC15-OSC32_OUT(PC15)-Pad9)") (class "Default")
      (node (ref "IC1") (pin "9") (pinfunction "PC15-OSC32_OUT(PC15)_9") (pintype "bidirectional"))
    )
    (net (code "128") (name "unconnected-(IC1A-PF0-Pad10)") (class "Default")
      (node (ref "IC1") (pin "10") (pinfunction "PF0_10") (pintype "bidirectional"))
    )
    (net (code "129") (name "unconnected-(IC1A-PF1-Pad11)") (class "Default")
      (node (ref "IC1") (pin "11") (pinfunction "PF1_11") (pintype "bidirectional"))
    )
    (net (code "130") (name "unconnected-(IC1A-PF2-Pad12)") (class "Default")
      (node (ref "IC1") (pin "12") (pinfunction "PF2_12") (pintype "bidirectional"))
    )
    (net (code "131") (name "unconnected-(IC1A-PF11-Pad49)") (class "Default")
      (node (ref "IC1") (pin "49") (pinfunction "PF11_49") (pintype "bidirectional"))
    )
    (net (code "132") (name "unconnected-(IC1A-PF12-Pad50)") (class "Default")
      (node (ref "IC1") (pin "50") (pinfunction "PF12_50") (pintype "bidirectional"))
    )
    (net (code "133") (name "unconnected-(IC1A-PF13-Pad53)") (class "Default")
      (node (ref "IC1") (pin "53") (pinfunction "PF13_53") (pintype "bidirectional"))
    )
    (net (code "134") (name "unconnected-(IC1A-PG2-Pad87)") (class "Default")
      (node (ref "IC1") (pin "87") (pinfunction "PG2_87") (pintype "bidirectional"))
    )
    (net (code "135") (name "unconnected-(IC1A-PG3-Pad88)") (class "Default")
      (node (ref "IC1") (pin "88") (pinfunction "PG3_88") (pintype "bidirectional"))
    )
    (net (code "136") (name "unconnected-(IC1A-PG7-Pad92)") (class "Default")
      (node (ref "IC1") (pin "92") (pinfunction "PG7_92") (pintype "bidirectional"))
    )
    (net (code "137") (name "unconnected-(IC1B-VBAT-Pad6)") (class "Default")
      (node (ref "IC1") (pin "6") (pinfunction "VBAT_6") (pintype "power_in"))
    )
    (net (code "138") (name "unconnected-(JP1-Pad7)") (class "Default")
      (node (ref "JP1") (pin "7") (pinfunction "7_7") (pintype "passive"))
    )
    (net (code "139") (name "unconnected-(JP1-Pad9)") (class "Default")
      (node (ref "JP1") (pin "9") (pinfunction "9_9") (pintype "passive"))
    )
  )
)
